# v1.net
KiCad netlist of a schematic drawn in EAGLE
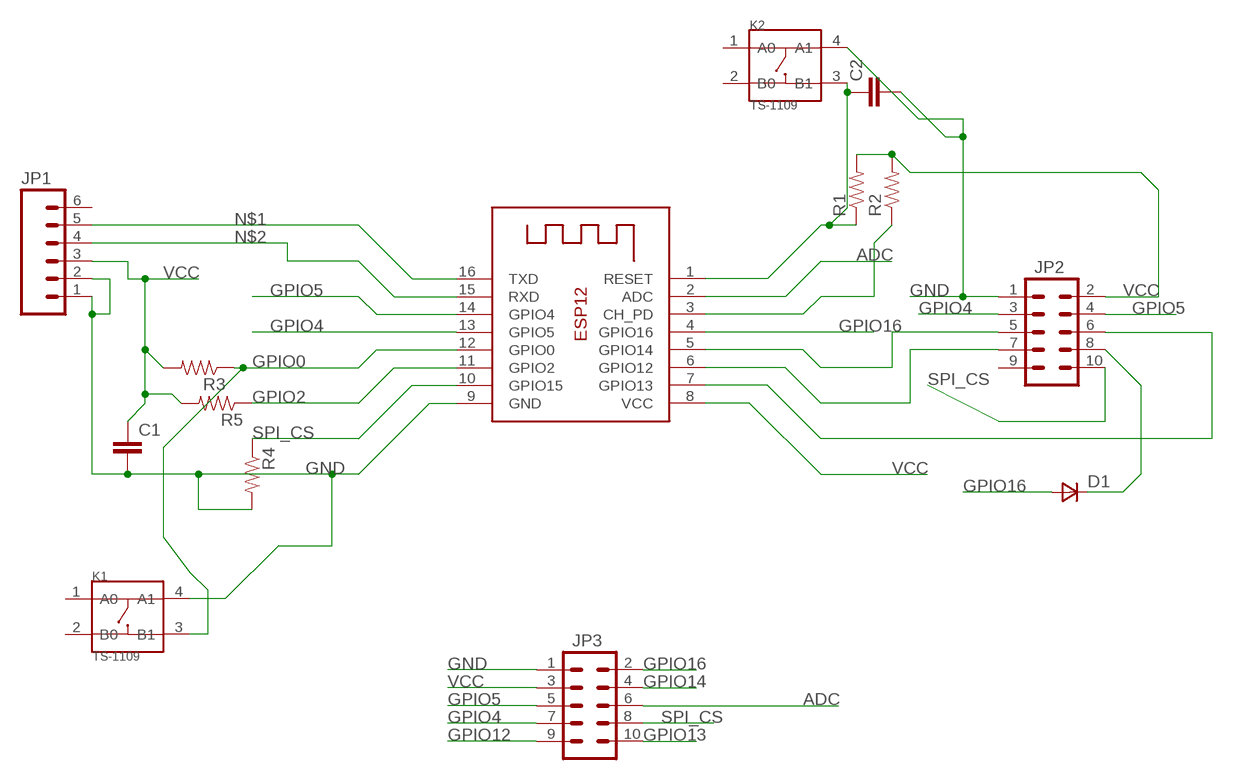
[diagram p0: schematic, sheet 1]

(export (version "E")
  (design (tool "Eeschema 10.0.6"))
  (components
    (comp (ref "C1")
      (value "CAP0805")
      (footprint "eagle-import:0805")
      (libsource (lib "eagle-import") (part "CAP0805"))
    )
    (comp (ref "C2")
      (value "CAP0805")
      (footprint "eagle-import:0805")
      (libsource (lib "eagle-import") (part "CAP0805"))
    )
    (comp (ref "D1")
      (value "DSOD323")
      (footprint "eagle-import:SOD323")
      (fields (field (name "MPN") "CDSOD323-T05C"))
      (libsource (lib "eagle-import") (part "DSOD323"))
    )
    (comp (ref "JP1")
      (value "M06SILK_FEMALE_PTH")
      (footprint "eagle-import:1X06")
      (libsource (lib "eagle-import") (part "M06SILK_FEMALE_PTH"))
    )
    (comp (ref "JP2")
      (value "M05X2PTH")
      (footprint "eagle-import:AVR_ICSP")
      (libsource (lib "eagle-import") (part "M05X2PTH"))
    )
    (comp (ref "JP3")
      (value "M05X2PTH")
      (footprint "eagle-import:AVR_ICSP")
      (libsource (lib "eagle-import") (part "M05X2PTH"))
    )
    (comp (ref "K1")
      (value "TS-1109")
      (footprint "eagle-import:SW4-6.0X6.0X5.0MM")
      (libsource (lib "eagle-import") (part "DIP-BUTTON-4P"))
    )
    (comp (ref "K2")
      (value "TS-1109")
      (footprint "eagle-import:SW4-6.0X6.0X5.0MM")
      (libsource (lib "eagle-import") (part "DIP-BUTTON-4P"))
    )
    (comp (ref "R1")
      (value "RESISTOR0805-RES")
      (footprint "eagle-import:0805")
      (libsource (lib "eagle-import") (part "RESISTOR0805-RES"))
    )
    (comp (ref "R2")
      (value "RESISTOR0805-RES")
      (footprint "eagle-import:0805")
      (libsource (lib "eagle-import") (part "RESISTOR0805-RES"))
    )
    (comp (ref "R3")
      (value "RESISTOR0805-RES")
      (footprint "eagle-import:0805")
      (libsource (lib "eagle-import") (part "RESISTOR0805-RES"))
    )
    (comp (ref "R4")
      (value "RESISTOR0805-RES")
      (footprint "eagle-import:0805")
      (libsource (lib "eagle-import") (part "RESISTOR0805-RES"))
    )
    (comp (ref "R5")
      (value "RESISTOR0805-RES")
      (footprint "eagle-import:0805")
      (libsource (lib "eagle-import") (part "RESISTOR0805-RES"))
    )
    (comp (ref "X1")
      (value "ESP-12")
      (footprint "eagle-import:ESP-12")
      (libsource (lib "eagle-import") (part "ESP-12"))
    )
  )
  (nets
    (net (code "1") (name "/ADC") (class "Default")
      (node (ref "JP3") (pin "6") (pinfunction "6_6") (pintype "passive"))
      (node (ref "X1") (pin "2") (pinfunction "ADC_2") (pintype "passive"))
    )
    (net (code "2") (name "/GND") (class "Default")
      (node (ref "C1") (pin "2") (pinfunction "2_2") (pintype "passive"))
      (node (ref "C2") (pin "2") (pinfunction "2_2") (pintype "passive"))
      (node (ref "JP1") (pin "1") (pinfunction "1_1") (pintype "passive"))
      (node (ref "JP1") (pin "2") (pinfunction "2_2") (pintype "passive"))
      (node (ref "JP2") (pin "1") (pinfunction "1_1") (pintype "passive"))
      (node (ref "JP3") (pin "1") (pinfunction "1_1") (pintype "passive"))
      (node (ref "K1") (pin "4") (pinfunction "A1_4") (pintype "bidirectional"))
      (node (ref "K2") (pin "4") (pinfunction "A1_4") (pintype "bidirectional"))
      (node (ref "R4") (pin "2") (pinfunction "2_2") (pintype "passive"))
      (node (ref "X1") (pin "9") (pinfunction "GND_9") (pintype "power_in"))
    )
    (net (code "3") (name "/GPIO0") (class "Default")
      (node (ref "K1") (pin "3") (pinfunction "B1_3") (pintype "bidirectional"))
      (node (ref "R3") (pin "1") (pinfunction "1_1") (pintype "passive"))
      (node (ref "X1") (pin "12") (pinfunction "GPIO0_12") (pintype "bidirectional"))
    )
    (net (code "4") (name "/GPIO2") (class "Default")
      (node (ref "R5") (pin "1") (pinfunction "1_1") (pintype "passive"))
      (node (ref "X1") (pin "11") (pinfunction "GPIO2_11") (pintype "bidirectional"))
    )
    (net (code "5") (name "/GPIO4") (class "Default")
      (node (ref "JP2") (pin "3") (pinfunction "3_3") (pintype "passive"))
      (node (ref "JP3") (pin "7") (pinfunction "7_7") (pintype "passive"))
      (node (ref "X1") (pin "13") (pinfunction "GPIO5_13") (pintype "bidirectional"))
    )
    (net (code "6") (name "/GPIO5") (class "Default")
      (node (ref "JP2") (pin "4") (pinfunction "4_4") (pintype "passive"))
      (node (ref "JP3") (pin "5") (pinfunction "5_5") (pintype "passive"))
      (node (ref "X1") (pin "14") (pinfunction "GPIO4_14") (pintype "bidirectional"))
    )
    (net (code "7") (name "/GPIO12") (class "Default")
      (node (ref "JP3") (pin "9") (pinfunction "9_9") (pintype "passive"))
    )
    (net (code "8") (name "/GPIO13") (class "Default")
      (node (ref "JP3") (pin "10") (pinfunction "10_10") (pintype "passive"))
    )
    (net (code "9") (name "/GPIO14") (class "Default")
      (node (ref "JP2") (pin "5") (pinfunction "5_5") (pintype "passive"))
      (node (ref "JP3") (pin "4") (pinfunction "4_4") (pintype "passive"))
      (node (ref "X1") (pin "5") (pinfunction "GPIO14_5") (pintype "bidirectional"))
    )
    (net (code "10") (name "/GPIO16") (class "Default")
      (node (ref "D1") (pin "2") (pinfunction "A_2") (pintype "passive"))
      (node (ref "JP3") (pin "2") (pinfunction "2_2") (pintype "passive"))
      (node (ref "X1") (pin "4") (pinfunction "GPIO16_4") (pintype "bidirectional"))
    )
    (net (code "11") (name "/N$1") (class "Default")
      (node (ref "JP1") (pin "5") (pinfunction "5_5") (pintype "passive"))
      (node (ref "X1") (pin "16") (pinfunction "TXD_16") (pintype "output"))
    )
    (net (code "12") (name "/N$2") (class "Default")
      (node (ref "JP1") (pin "4") (pinfunction "4_4") (pintype "passive"))
      (node (ref "X1") (pin "15") (pinfunction "RXD_15") (pintype "input"))
    )
    (net (code "13") (name "/SPI_CS") (class "Default")
      (node (ref "JP2") (pin "10") (pinfunction "10_10") (pintype "passive"))
      (node (ref "JP3") (pin "8") (pinfunction "8_8") (pintype "passive"))
      (node (ref "R4") (pin "1") (pinfunction "1_1") (pintype "passive"))
      (node (ref "X1") (pin "10") (pinfunction "GPIO15_10") (pintype "bidirectional"))
    )
    (net (code "14") (name "/VCC") (class "Default")
      (node (ref "C1") (pin "1") (pinfunction "1_1") (pintype "passive"))
      (node (ref "JP1") (pin "3") (pinfunction "3_3") (pintype "passive"))
      (node (ref "JP2") (pin "2") (pinfunction "2_2") (pintype "passive"))
      (node (ref "JP3") (pin "3") (pinfunction "3_3") (pintype "passive"))
      (node (ref "R1") (pin "2") (pinfunction "2_2") (pintype "passive"))
      (node (ref "R2") (pin "2") (pinfunction "2_2") (pintype "passive"))
      (node (ref "R3") (pin "2") (pinfunction "2_2") (pintype "passive"))
      (node (ref "R5") (pin "2") (pinfunction "2_2") (pintype "passive"))
      (node (ref "X1") (pin "8") (pinfunction "VCC_8") (pintype "power_in"))
    )
    (net (code "15") (name "Net-(D1-C)") (class "Default")
      (node (ref "D1") (pin "1") (pinfunction "C_1") (pintype "passive"))
      (node (ref "JP2") (pin "8") (pinfunction "8_8") (pintype "passive"))
    )
    (net (code "16") (name "Net-(K2-B1)") (class "Default")
      (node (ref "C2") (pin "1") (pinfunction "1_1") (pintype "passive"))
      (node (ref "K2") (pin "3") (pinfunction "B1_3") (pintype "bidirectional"))
      (node (ref "R1") (pin "1") (pinfunction "1_1") (pintype "passive"))
      (node (ref "X1") (pin "1") (pinfunction "RESET_1") (pintype "input"))
    )
    (net (code "17") (name "Net-(X1-CH_PD)") (class "Default")
      (node (ref "R2") (pin "1") (pinfunction "1_1") (pintype "passive"))
      (node (ref "X1") (pin "3") (pinfunction "CH_PD_3") (pintype "input"))
    )
    (net (code "18") (name "Net-(X1-GPIO12)") (class "Default")
      (node (ref "JP2") (pin "7") (pinfunction "7_7") (pintype "passive"))
      (node (ref "X1") (pin "6") (pinfunction "GPIO12_6") (pintype "bidirectional"))
    )
    (net (code "19") (name "Net-(X1-GPIO13)") (class "Default")
      (node (ref "JP2") (pin "6") (pinfunction "6_6") (pintype "passive"))
      (node (ref "X1") (pin "7") (pinfunction "GPIO13_7") (pintype "bidirectional"))
    )
    (net (code "20") (name "unconnected-(JP1-Pad6)") (class "Default")
      (node (ref "JP1") (pin "6") (pinfunction "6_6") (pintype "passive"))
    )
    (net (code "21") (name "unconnected-(JP2-Pad9)") (class "Default")
      (node (ref "JP2") (pin "9") (pinfunction "9_9") (pintype "passive"))
    )
    (net (code "22") (name "unconnected-(K1-A0-Pad1)") (class "Default")
      (node (ref "K1") (pin "1") (pinfunction "A0_1") (pintype "bidirectional"))
    )
    (net (code "23") (name "unconnected-(K1-B0-Pad2)") (class "Default")
      (node (ref "K1") (pin "2") (pinfunction "B0_2") (pintype "bidirectional"))
    )
    (net (code "24") (name "unconnected-(K2-A0-Pad1)") (class "Default")
      (node (ref "K2") (pin "1") (pinfunction "A0_1") (pintype "bidirectional"))
    )
    (net (code "25") (name "unconnected-(K2-B0-Pad2)") (class "Default")
      (node (ref "K2") (pin "2") (pinfunction "B0_2") (pintype "bidirectional"))
    )
  )
)
